# LED_Driver_and_LEDs_04.net
KiCad netlist of a schematic drawn in Altium Designer
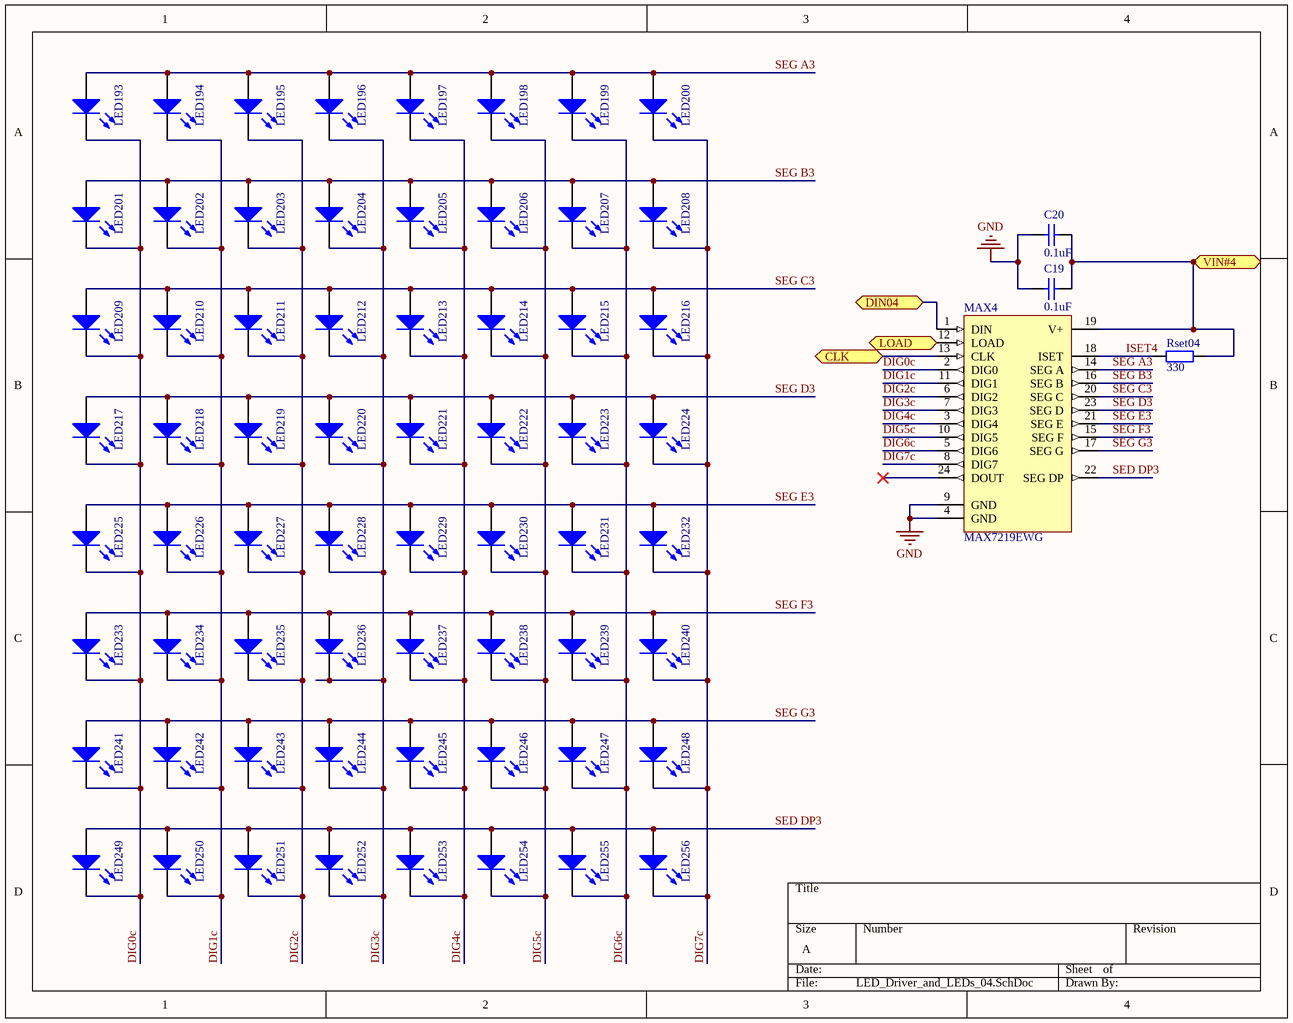
[diagram p0: LED_Driver_and_LEDs_04.SchDoc]

(export (version "E")
  (design (tool "Eeschema 10.0.6"))
  (components
    (comp (ref "C19")
      (value "0.1uF")
      (footprint "6-0805_N")
      (description "Capacitor (Semiconductor SIM Model)")
      (fields (field (name "Comment") "Cap Semi") (field (name "PUBLISHER") "Altium Limited"))
      (libsource (lib "Miscellaneous Devices") (part "Cap Semi"))
    )
    (comp (ref "C20")
      (value "0.1uF")
      (footprint "6-0805_N")
      (description "Capacitor (Semiconductor SIM Model)")
      (fields (field (name "Comment") "Cap Semi") (field (name "PUBLISHER") "Altium Limited"))
      (libsource (lib "Miscellaneous Devices") (part "Cap Semi"))
    )
    (comp (ref "LED193")
      (value "LED3")
      (footprint "3.5X2.8X1.9")
      (description "Typical BLUE SiC LED")
      (fields (field (name "PUBLISHER") "Altium Limited"))
      (libsource (lib "Miscellaneous Devices") (part "LED3"))
    )
    (comp (ref "LED194")
      (value "LED3")
      (footprint "3.5X2.8X1.9")
      (description "Typical BLUE SiC LED")
      (fields (field (name "PUBLISHER") "Altium Limited"))
      (libsource (lib "Miscellaneous Devices") (part "LED3"))
    )
    (comp (ref "LED195")
      (value "LED3")
      (footprint "3.5X2.8X1.9")
      (description "Typical BLUE SiC LED")
      (fields (field (name "PUBLISHER") "Altium Limited"))
      (libsource (lib "Miscellaneous Devices") (part "LED3"))
    )
    (comp (ref "LED196")
      (value "LED3")
      (footprint "3.5X2.8X1.9")
      (description "Typical BLUE SiC LED")
      (fields (field (name "PUBLISHER") "Altium Limited"))
      (libsource (lib "Miscellaneous Devices") (part "LED3"))
    )
    (comp (ref "LED197")
      (value "LED3")
      (footprint "3.5X2.8X1.9")
      (description "Typical BLUE SiC LED")
      (fields (field (name "PUBLISHER") "Altium Limited"))
      (libsource (lib "Miscellaneous Devices") (part "LED3"))
    )
    (comp (ref "LED198")
      (value "LED3")
      (footprint "3.5X2.8X1.9")
      (description "Typical BLUE SiC LED")
      (fields (field (name "PUBLISHER") "Altium Limited"))
      (libsource (lib "Miscellaneous Devices") (part "LED3"))
    )
    (comp (ref "LED199")
      (value "LED3")
      (footprint "3.5X2.8X1.9")
      (description "Typical BLUE SiC LED")
      (fields (field (name "PUBLISHER") "Altium Limited"))
      (libsource (lib "Miscellaneous Devices") (part "LED3"))
    )
    (comp (ref "LED200")
      (value "LED3")
      (footprint "3.5X2.8X1.9")
      (description "Typical BLUE SiC LED")
      (fields (field (name "PUBLISHER") "Altium Limited"))
      (libsource (lib "Miscellaneous Devices") (part "LED3"))
    )
    (comp (ref "LED201")
      (value "LED3")
      (footprint "3.5X2.8X1.9")
      (description "Typical BLUE SiC LED")
      (fields (field (name "PUBLISHER") "Altium Limited"))
      (libsource (lib "Miscellaneous Devices") (part "LED3"))
    )
    (comp (ref "LED202")
      (value "LED3")
      (footprint "3.5X2.8X1.9")
      (description "Typical BLUE SiC LED")
      (fields (field (name "PUBLISHER") "Altium Limited"))
      (libsource (lib "Miscellaneous Devices") (part "LED3"))
    )
    (comp (ref "LED203")
      (value "LED3")
      (footprint "3.5X2.8X1.9")
      (description "Typical BLUE SiC LED")
      (fields (field (name "PUBLISHER") "Altium Limited"))
      (libsource (lib "Miscellaneous Devices") (part "LED3"))
    )
    (comp (ref "LED204")
      (value "LED3")
      (footprint "3.5X2.8X1.9")
      (description "Typical BLUE SiC LED")
      (fields (field (name "PUBLISHER") "Altium Limited"))
      (libsource (lib "Miscellaneous Devices") (part "LED3"))
    )
    (comp (ref "LED205")
      (value "LED3")
      (footprint "3.5X2.8X1.9")
      (description "Typical BLUE SiC LED")
      (fields (field (name "PUBLISHER") "Altium Limited"))
      (libsource (lib "Miscellaneous Devices") (part "LED3"))
    )
    (comp (ref "LED206")
      (value "LED3")
      (footprint "3.5X2.8X1.9")
      (description "Typical BLUE SiC LED")
      (fields (field (name "PUBLISHER") "Altium Limited"))
      (libsource (lib "Miscellaneous Devices") (part "LED3"))
    )
    (comp (ref "LED207")
      (value "LED3")
      (footprint "3.5X2.8X1.9")
      (description "Typical BLUE SiC LED")
      (fields (field (name "PUBLISHER") "Altium Limited"))
      (libsource (lib "Miscellaneous Devices") (part "LED3"))
    )
    (comp (ref "LED208")
      (value "LED3")
      (footprint "3.5X2.8X1.9")
      (description "Typical BLUE SiC LED")
      (fields (field (name "PUBLISHER") "Altium Limited"))
      (libsource (lib "Miscellaneous Devices") (part "LED3"))
    )
    (comp (ref "LED209")
      (value "LED3")
      (footprint "3.5X2.8X1.9")
      (description "Typical BLUE SiC LED")
      (fields (field (name "PUBLISHER") "Altium Limited"))
      (libsource (lib "Miscellaneous Devices") (part "LED3"))
    )
    (comp (ref "LED210")
      (value "LED3")
      (footprint "3.5X2.8X1.9")
      (description "Typical BLUE SiC LED")
      (fields (field (name "PUBLISHER") "Altium Limited"))
      (libsource (lib "Miscellaneous Devices") (part "LED3"))
    )
    (comp (ref "LED211")
      (value "LED3")
      (footprint "3.5X2.8X1.9")
      (description "Typical BLUE SiC LED")
      (fields (field (name "PUBLISHER") "Altium Limited"))
      (libsource (lib "Miscellaneous Devices") (part "LED3"))
    )
    (comp (ref "LED212")
      (value "LED3")
      (footprint "3.5X2.8X1.9")
      (description "Typical BLUE SiC LED")
      (fields (field (name "PUBLISHER") "Altium Limited"))
      (libsource (lib "Miscellaneous Devices") (part "LED3"))
    )
    (comp (ref "LED213")
      (value "LED3")
      (footprint "3.5X2.8X1.9")
      (description "Typical BLUE SiC LED")
      (fields (field (name "PUBLISHER") "Altium Limited"))
      (libsource (lib "Miscellaneous Devices") (part "LED3"))
    )
    (comp (ref "LED214")
      (value "LED3")
      (footprint "3.5X2.8X1.9")
      (description "Typical BLUE SiC LED")
      (fields (field (name "PUBLISHER") "Altium Limited"))
      (libsource (lib "Miscellaneous Devices") (part "LED3"))
    )
    (comp (ref "LED215")
      (value "LED3")
      (footprint "3.5X2.8X1.9")
      (description "Typical BLUE SiC LED")
      (fields (field (name "PUBLISHER") "Altium Limited"))
      (libsource (lib "Miscellaneous Devices") (part "LED3"))
    )
    (comp (ref "LED216")
      (value "LED3")
      (footprint "3.5X2.8X1.9")
      (description "Typical BLUE SiC LED")
      (fields (field (name "PUBLISHER") "Altium Limited"))
      (libsource (lib "Miscellaneous Devices") (part "LED3"))
    )
    (comp (ref "LED217")
      (value "LED3")
      (footprint "3.5X2.8X1.9")
      (description "Typical BLUE SiC LED")
      (fields (field (name "PUBLISHER") "Altium Limited"))
      (libsource (lib "Miscellaneous Devices") (part "LED3"))
    )
    (comp (ref "LED218")
      (value "LED3")
      (footprint "3.5X2.8X1.9")
      (description "Typical BLUE SiC LED")
      (fields (field (name "PUBLISHER") "Altium Limited"))
      (libsource (lib "Miscellaneous Devices") (part "LED3"))
    )
    (comp (ref "LED219")
      (value "LED3")
      (footprint "3.5X2.8X1.9")
      (description "Typical BLUE SiC LED")
      (fields (field (name "PUBLISHER") "Altium Limited"))
      (libsource (lib "Miscellaneous Devices") (part "LED3"))
    )
    (comp (ref "LED220")
      (value "LED3")
      (footprint "3.5X2.8X1.9")
      (description "Typical BLUE SiC LED")
      (fields (field (name "PUBLISHER") "Altium Limited"))
      (libsource (lib "Miscellaneous Devices") (part "LED3"))
    )
    (comp (ref "LED221")
      (value "LED3")
      (footprint "3.5X2.8X1.9")
      (description "Typical BLUE SiC LED")
      (fields (field (name "PUBLISHER") "Altium Limited"))
      (libsource (lib "Miscellaneous Devices") (part "LED3"))
    )
    (comp (ref "LED222")
      (value "LED3")
      (footprint "3.5X2.8X1.9")
      (description "Typical BLUE SiC LED")
      (fields (field (name "PUBLISHER") "Altium Limited"))
      (libsource (lib "Miscellaneous Devices") (part "LED3"))
    )
    (comp (ref "LED223")
      (value "LED3")
      (footprint "3.5X2.8X1.9")
      (description "Typical BLUE SiC LED")
      (fields (field (name "PUBLISHER") "Altium Limited"))
      (libsource (lib "Miscellaneous Devices") (part "LED3"))
    )
    (comp (ref "LED224")
      (value "LED3")
      (footprint "3.5X2.8X1.9")
      (description "Typical BLUE SiC LED")
      (fields (field (name "PUBLISHER") "Altium Limited"))
      (libsource (lib "Miscellaneous Devices") (part "LED3"))
    )
    (comp (ref "LED225")
      (value "LED3")
      (footprint "3.5X2.8X1.9")
      (description "Typical BLUE SiC LED")
      (fields (field (name "PUBLISHER") "Altium Limited"))
      (libsource (lib "Miscellaneous Devices") (part "LED3"))
    )
    (comp (ref "LED226")
      (value "LED3")
      (footprint "3.5X2.8X1.9")
      (description "Typical BLUE SiC LED")
      (fields (field (name "PUBLISHER") "Altium Limited"))
      (libsource (lib "Miscellaneous Devices") (part "LED3"))
    )
    (comp (ref "LED227")
      (value "LED3")
      (footprint "3.5X2.8X1.9")
      (description "Typical BLUE SiC LED")
      (fields (field (name "PUBLISHER") "Altium Limited"))
      (libsource (lib "Miscellaneous Devices") (part "LED3"))
    )
    (comp (ref "LED228")
      (value "LED3")
      (footprint "3.5X2.8X1.9")
      (description "Typical BLUE SiC LED")
      (fields (field (name "PUBLISHER") "Altium Limited"))
      (libsource (lib "Miscellaneous Devices") (part "LED3"))
    )
    (comp (ref "LED229")
      (value "LED3")
      (footprint "3.5X2.8X1.9")
      (description "Typical BLUE SiC LED")
      (fields (field (name "PUBLISHER") "Altium Limited"))
      (libsource (lib "Miscellaneous Devices") (part "LED3"))
    )
    (comp (ref "LED230")
      (value "LED3")
      (footprint "3.5X2.8X1.9")
      (description "Typical BLUE SiC LED")
      (fields (field (name "PUBLISHER") "Altium Limited"))
      (libsource (lib "Miscellaneous Devices") (part "LED3"))
    )
    (comp (ref "LED231")
      (value "LED3")
      (footprint "3.5X2.8X1.9")
      (description "Typical BLUE SiC LED")
      (fields (field (name "PUBLISHER") "Altium Limited"))
      (libsource (lib "Miscellaneous Devices") (part "LED3"))
    )
    (comp (ref "LED232")
      (value "LED3")
      (footprint "3.5X2.8X1.9")
      (description "Typical BLUE SiC LED")
      (fields (field (name "PUBLISHER") "Altium Limited"))
      (libsource (lib "Miscellaneous Devices") (part "LED3"))
    )
    (comp (ref "LED233")
      (value "LED3")
      (footprint "3.5X2.8X1.9")
      (description "Typical BLUE SiC LED")
      (fields (field (name "PUBLISHER") "Altium Limited"))
      (libsource (lib "Miscellaneous Devices") (part "LED3"))
    )
    (comp (ref "LED234")
      (value "LED3")
      (footprint "3.5X2.8X1.9")
      (description "Typical BLUE SiC LED")
      (fields (field (name "PUBLISHER") "Altium Limited"))
      (libsource (lib "Miscellaneous Devices") (part "LED3"))
    )
    (comp (ref "LED235")
      (value "LED3")
      (footprint "3.5X2.8X1.9")
      (description "Typical BLUE SiC LED")
      (fields (field (name "PUBLISHER") "Altium Limited"))
      (libsource (lib "Miscellaneous Devices") (part "LED3"))
    )
    (comp (ref "LED236")
      (value "LED3")
      (footprint "3.5X2.8X1.9")
      (description "Typical BLUE SiC LED")
      (fields (field (name "PUBLISHER") "Altium Limited"))
      (libsource (lib "Miscellaneous Devices") (part "LED3"))
    )
    (comp (ref "LED237")
      (value "LED3")
      (footprint "3.5X2.8X1.9")
      (description "Typical BLUE SiC LED")
      (fields (field (name "PUBLISHER") "Altium Limited"))
      (libsource (lib "Miscellaneous Devices") (part "LED3"))
    )
    (comp (ref "LED238")
      (value "LED3")
      (footprint "3.5X2.8X1.9")
      (description "Typical BLUE SiC LED")
      (fields (field (name "PUBLISHER") "Altium Limited"))
      (libsource (lib "Miscellaneous Devices") (part "LED3"))
    )
    (comp (ref "LED239")
      (value "LED3")
      (footprint "3.5X2.8X1.9")
      (description "Typical BLUE SiC LED")
      (fields (field (name "PUBLISHER") "Altium Limited"))
      (libsource (lib "Miscellaneous Devices") (part "LED3"))
    )
    (comp (ref "LED240")
      (value "LED3")
      (footprint "3.5X2.8X1.9")
      (description "Typical BLUE SiC LED")
      (fields (field (name "PUBLISHER") "Altium Limited"))
      (libsource (lib "Miscellaneous Devices") (part "LED3"))
    )
    (comp (ref "LED241")
      (value "LED3")
      (footprint "3.5X2.8X1.9")
      (description "Typical BLUE SiC LED")
      (fields (field (name "PUBLISHER") "Altium Limited"))
      (libsource (lib "Miscellaneous Devices") (part "LED3"))
    )
    (comp (ref "LED242")
      (value "LED3")
      (footprint "3.5X2.8X1.9")
      (description "Typical BLUE SiC LED")
      (fields (field (name "PUBLISHER") "Altium Limited"))
      (libsource (lib "Miscellaneous Devices") (part "LED3"))
    )
    (comp (ref "LED243")
      (value "LED3")
      (footprint "3.5X2.8X1.9")
      (description "Typical BLUE SiC LED")
      (fields (field (name "PUBLISHER") "Altium Limited"))
      (libsource (lib "Miscellaneous Devices") (part "LED3"))
    )
    (comp (ref "LED244")
      (value "LED3")
      (footprint "3.5X2.8X1.9")
      (description "Typical BLUE SiC LED")
      (fields (field (name "PUBLISHER") "Altium Limited"))
      (libsource (lib "Miscellaneous Devices") (part "LED3"))
    )
    (comp (ref "LED245")
      (value "LED3")
      (footprint "3.5X2.8X1.9")
      (description "Typical BLUE SiC LED")
      (fields (field (name "PUBLISHER") "Altium Limited"))
      (libsource (lib "Miscellaneous Devices") (part "LED3"))
    )
    (comp (ref "LED246")
      (value "LED3")
      (footprint "3.5X2.8X1.9")
      (description "Typical BLUE SiC LED")
      (fields (field (name "PUBLISHER") "Altium Limited"))
      (libsource (lib "Miscellaneous Devices") (part "LED3"))
    )
    (comp (ref "LED247")
      (value "LED3")
      (footprint "3.5X2.8X1.9")
      (description "Typical BLUE SiC LED")
      (fields (field (name "PUBLISHER") "Altium Limited"))
      (libsource (lib "Miscellaneous Devices") (part "LED3"))
    )
    (comp (ref "LED248")
      (value "LED3")
      (footprint "3.5X2.8X1.9")
      (description "Typical BLUE SiC LED")
      (fields (field (name "PUBLISHER") "Altium Limited"))
      (libsource (lib "Miscellaneous Devices") (part "LED3"))
    )
    (comp (ref "LED249")
      (value "LED3")
      (footprint "3.5X2.8X1.9")
      (description "Typical BLUE SiC LED")
      (fields (field (name "PUBLISHER") "Altium Limited"))
      (libsource (lib "Miscellaneous Devices") (part "LED3"))
    )
    (comp (ref "LED250")
      (value "LED3")
      (footprint "3.5X2.8X1.9")
      (description "Typical BLUE SiC LED")
      (fields (field (name "PUBLISHER") "Altium Limited"))
      (libsource (lib "Miscellaneous Devices") (part "LED3"))
    )
    (comp (ref "LED251")
      (value "LED3")
      (footprint "3.5X2.8X1.9")
      (description "Typical BLUE SiC LED")
      (fields (field (name "PUBLISHER") "Altium Limited"))
      (libsource (lib "Miscellaneous Devices") (part "LED3"))
    )
    (comp (ref "LED252")
      (value "LED3")
      (footprint "3.5X2.8X1.9")
      (description "Typical BLUE SiC LED")
      (fields (field (name "PUBLISHER") "Altium Limited"))
      (libsource (lib "Miscellaneous Devices") (part "LED3"))
    )
    (comp (ref "LED253")
      (value "LED3")
      (footprint "3.5X2.8X1.9")
      (description "Typical BLUE SiC LED")
      (fields (field (name "PUBLISHER") "Altium Limited"))
      (libsource (lib "Miscellaneous Devices") (part "LED3"))
    )
    (comp (ref "LED254")
      (value "LED3")
      (footprint "3.5X2.8X1.9")
      (description "Typical BLUE SiC LED")
      (fields (field (name "PUBLISHER") "Altium Limited"))
      (libsource (lib "Miscellaneous Devices") (part "LED3"))
    )
    (comp (ref "LED255")
      (value "LED3")
      (footprint "3.5X2.8X1.9")
      (description "Typical BLUE SiC LED")
      (fields (field (name "PUBLISHER") "Altium Limited"))
      (libsource (lib "Miscellaneous Devices") (part "LED3"))
    )
    (comp (ref "LED256")
      (value "LED3")
      (footprint "3.5X2.8X1.9")
      (description "Typical BLUE SiC LED")
      (fields (field (name "PUBLISHER") "Altium Limited"))
      (libsource (lib "Miscellaneous Devices") (part "LED3"))
    )
    (comp (ref "MAX4")
      (value "MAX7219EWG")
      (footprint "WSO24_N")
      (description "Serially Interfaced, 8-Digit LED Display Driver")
      (fields (field (name "PUBLISHER") "Altium Limited"))
      (libsource (lib "Maxim Interface Display Driver") (part "MAX7219EWG"))
    )
    (comp (ref "Rset04")
      (value "330")
      (footprint "J1-0603")
      (description "Resistor")
      (fields (field (name "Comment") "Res2") (field (name "PUBLISHER") "Altium Limited"))
      (libsource (lib "Miscellaneous Devices") (part "Res2"))
    )
  )
  (nets
    (net (code "1") (name "/CLK") (class "Default")
      (node (ref "MAX4") (pin "13") (pinfunction "CLK_13") (pintype "input"))
    )
    (net (code "2") (name "/DIG0c") (class "Default")
      (node (ref "LED193") (pin "2") (pinfunction "K_2") (pintype "passive"))
      (node (ref "LED201") (pin "2") (pinfunction "K_2") (pintype "passive"))
      (node (ref "LED209") (pin "2") (pinfunction "K_2") (pintype "passive"))
      (node (ref "LED217") (pin "2") (pinfunction "K_2") (pintype "passive"))
      (node (ref "LED225") (pin "2") (pinfunction "K_2") (pintype "passive"))
      (node (ref "LED233") (pin "2") (pinfunction "K_2") (pintype "passive"))
      (node (ref "LED241") (pin "2") (pinfunction "K_2") (pintype "passive"))
      (node (ref "LED249") (pin "2") (pinfunction "K_2") (pintype "passive"))
      (node (ref "MAX4") (pin "2") (pinfunction "DIG0_2") (pintype "output"))
    )
    (net (code "3") (name "/DIG1c") (class "Default")
      (node (ref "LED194") (pin "2") (pinfunction "K_2") (pintype "passive"))
      (node (ref "LED202") (pin "2") (pinfunction "K_2") (pintype "passive"))
      (node (ref "LED210") (pin "2") (pinfunction "K_2") (pintype "passive"))
      (node (ref "LED218") (pin "2") (pinfunction "K_2") (pintype "passive"))
      (node (ref "LED226") (pin "2") (pinfunction "K_2") (pintype "passive"))
      (node (ref "LED234") (pin "2") (pinfunction "K_2") (pintype "passive"))
      (node (ref "LED242") (pin "2") (pinfunction "K_2") (pintype "passive"))
      (node (ref "LED250") (pin "2") (pinfunction "K_2") (pintype "passive"))
      (node (ref "MAX4") (pin "11") (pinfunction "DIG1_11") (pintype "output"))
    )
    (net (code "4") (name "/DIG2c") (class "Default")
      (node (ref "LED195") (pin "2") (pinfunction "K_2") (pintype "passive"))
      (node (ref "LED203") (pin "2") (pinfunction "K_2") (pintype "passive"))
      (node (ref "LED211") (pin "2") (pinfunction "K_2") (pintype "passive"))
      (node (ref "LED219") (pin "2") (pinfunction "K_2") (pintype "passive"))
      (node (ref "LED227") (pin "2") (pinfunction "K_2") (pintype "passive"))
      (node (ref "LED235") (pin "2") (pinfunction "K_2") (pintype "passive"))
      (node (ref "LED243") (pin "2") (pinfunction "K_2") (pintype "passive"))
      (node (ref "LED251") (pin "2") (pinfunction "K_2") (pintype "passive"))
      (node (ref "MAX4") (pin "6") (pinfunction "DIG2_6") (pintype "output"))
    )
    (net (code "5") (name "/DIG3c") (class "Default")
      (node (ref "LED196") (pin "2") (pinfunction "K_2") (pintype "passive"))
      (node (ref "LED204") (pin "2") (pinfunction "K_2") (pintype "passive"))
      (node (ref "LED212") (pin "2") (pinfunction "K_2") (pintype "passive"))
      (node (ref "LED220") (pin "2") (pinfunction "K_2") (pintype "passive"))
      (node (ref "LED228") (pin "2") (pinfunction "K_2") (pintype "passive"))
      (node (ref "LED236") (pin "2") (pinfunction "K_2") (pintype "passive"))
      (node (ref "LED244") (pin "2") (pinfunction "K_2") (pintype "passive"))
      (node (ref "LED252") (pin "2") (pinfunction "K_2") (pintype "passive"))
      (node (ref "MAX4") (pin "7") (pinfunction "DIG3_7") (pintype "output"))
    )
    (net (code "6") (name "/DIG4c") (class "Default")
      (node (ref "LED197") (pin "2") (pinfunction "K_2") (pintype "passive"))
      (node (ref "LED205") (pin "2") (pinfunction "K_2") (pintype "passive"))
      (node (ref "LED213") (pin "2") (pinfunction "K_2") (pintype "passive"))
      (node (ref "LED221") (pin "2") (pinfunction "K_2") (pintype "passive"))
      (node (ref "LED229") (pin "2") (pinfunction "K_2") (pintype "passive"))
      (node (ref "LED237") (pin "2") (pinfunction "K_2") (pintype "passive"))
      (node (ref "LED245") (pin "2") (pinfunction "K_2") (pintype "passive"))
      (node (ref "LED253") (pin "2") (pinfunction "K_2") (pintype "passive"))
      (node (ref "MAX4") (pin "3") (pinfunction "DIG4_3") (pintype "output"))
    )
    (net (code "7") (name "/DIG5c") (class "Default")
      (node (ref "LED198") (pin "2") (pinfunction "K_2") (pintype "passive"))
      (node (ref "LED206") (pin "2") (pinfunction "K_2") (pintype "passive"))
      (node (ref "LED214") (pin "2") (pinfunction "K_2") (pintype "passive"))
      (node (ref "LED222") (pin "2") (pinfunction "K_2") (pintype "passive"))
      (node (ref "LED230") (pin "2") (pinfunction "K_2") (pintype "passive"))
      (node (ref "LED238") (pin "2") (pinfunction "K_2") (pintype "passive"))
      (node (ref "LED246") (pin "2") (pinfunction "K_2") (pintype "passive"))
      (node (ref "LED254") (pin "2") (pinfunction "K_2") (pintype "passive"))
      (node (ref "MAX4") (pin "10") (pinfunction "DIG5_10") (pintype "output"))
    )
    (net (code "8") (name "/DIG6c") (class "Default")
      (node (ref "LED199") (pin "2") (pinfunction "K_2") (pintype "passive"))
      (node (ref "LED207") (pin "2") (pinfunction "K_2") (pintype "passive"))
      (node (ref "LED215") (pin "2") (pinfunction "K_2") (pintype "passive"))
      (node (ref "LED223") (pin "2") (pinfunction "K_2") (pintype "passive"))
      (node (ref "LED231") (pin "2") (pinfunction "K_2") (pintype "passive"))
      (node (ref "LED239") (pin "2") (pinfunction "K_2") (pintype "passive"))
      (node (ref "LED247") (pin "2") (pinfunction "K_2") (pintype "passive"))
      (node (ref "LED255") (pin "2") (pinfunction "K_2") (pintype "passive"))
      (node (ref "MAX4") (pin "5") (pinfunction "DIG6_5") (pintype "output"))
    )
    (net (code "9") (name "/DIG7c") (class "Default")
      (node (ref "LED200") (pin "2") (pinfunction "K_2") (pintype "passive"))
      (node (ref "LED208") (pin "2") (pinfunction "K_2") (pintype "passive"))
      (node (ref "LED216") (pin "2") (pinfunction "K_2") (pintype "passive"))
      (node (ref "LED224") (pin "2") (pinfunction "K_2") (pintype "passive"))
      (node (ref "LED232") (pin "2") (pinfunction "K_2") (pintype "passive"))
      (node (ref "LED240") (pin "2") (pinfunction "K_2") (pintype "passive"))
      (node (ref "LED248") (pin "2") (pinfunction "K_2") (pintype "passive"))
      (node (ref "LED256") (pin "2") (pinfunction "K_2") (pintype "passive"))
      (node (ref "MAX4") (pin "8") (pinfunction "DIG7_8") (pintype "output"))
    )
    (net (code "10") (name "/DIN04") (class "Default")
      (node (ref "MAX4") (pin "1") (pinfunction "DIN_1") (pintype "input"))
    )
    (net (code "11") (name "/ISET4") (class "Default")
      (node (ref "MAX4") (pin "18") (pinfunction "ISET_18") (pintype "passive"))
      (node (ref "Rset04") (pin "2") (pinfunction "2_2") (pintype "passive"))
    )
    (net (code "12") (name "/LOAD") (class "Default")
      (node (ref "MAX4") (pin "12") (pinfunction "LOAD_12") (pintype "input"))
    )
    (net (code "13") (name "/SED DP3") (class "Default")
      (node (ref "LED249") (pin "1") (pinfunction "A_1") (pintype "passive"))
      (node (ref "LED250") (pin "1") (pinfunction "A_1") (pintype "passive"))
      (node (ref "LED251") (pin "1") (pinfunction "A_1") (pintype "passive"))
      (node (ref "LED252") (pin "1") (pinfunction "A_1") (pintype "passive"))
      (node (ref "LED253") (pin "1") (pinfunction "A_1") (pintype "passive"))
      (node (ref "LED254") (pin "1") (pinfunction "A_1") (pintype "passive"))
      (node (ref "LED255") (pin "1") (pinfunction "A_1") (pintype "passive"))
      (node (ref "LED256") (pin "1") (pinfunction "A_1") (pintype "passive"))
      (node (ref "MAX4") (pin "22") (pinfunction "SEG_DP_22") (pintype "output"))
    )
    (net (code "14") (name "/SEG A3") (class "Default")
      (node (ref "LED193") (pin "1") (pinfunction "A_1") (pintype "passive"))
      (node (ref "LED194") (pin "1") (pinfunction "A_1") (pintype "passive"))
      (node (ref "LED195") (pin "1") (pinfunction "A_1") (pintype "passive"))
      (node (ref "LED196") (pin "1") (pinfunction "A_1") (pintype "passive"))
      (node (ref "LED197") (pin "1") (pinfunction "A_1") (pintype "passive"))
      (node (ref "LED198") (pin "1") (pinfunction "A_1") (pintype "passive"))
      (node (ref "LED199") (pin "1") (pinfunction "A_1") (pintype "passive"))
      (node (ref "LED200") (pin "1") (pinfunction "A_1") (pintype "passive"))
      (node (ref "MAX4") (pin "14") (pinfunction "SEG_A_14") (pintype "output"))
    )
    (net (code "15") (name "/SEG B3") (class "Default")
      (node (ref "LED201") (pin "1") (pinfunction "A_1") (pintype "passive"))
      (node (ref "LED202") (pin "1") (pinfunction "A_1") (pintype "passive"))
      (node (ref "LED203") (pin "1") (pinfunction "A_1") (pintype "passive"))
      (node (ref "LED204") (pin "1") (pinfunction "A_1") (pintype "passive"))
      (node (ref "LED205") (pin "1") (pinfunction "A_1") (pintype "passive"))
      (node (ref "LED206") (pin "1") (pinfunction "A_1") (pintype "passive"))
      (node (ref "LED207") (pin "1") (pinfunction "A_1") (pintype "passive"))
      (node (ref "LED208") (pin "1") (pinfunction "A_1") (pintype "passive"))
      (node (ref "MAX4") (pin "16") (pinfunction "SEG_B_16") (pintype "output"))
    )
    (net (code "16") (name "/SEG C3") (class "Default")
      (node (ref "LED209") (pin "1") (pinfunction "A_1") (pintype "passive"))
      (node (ref "LED210") (pin "1") (pinfunction "A_1") (pintype "passive"))
      (node (ref "LED211") (pin "1") (pinfunction "A_1") (pintype "passive"))
      (node (ref "LED212") (pin "1") (pinfunction "A_1") (pintype "passive"))
      (node (ref "LED213") (pin "1") (pinfunction "A_1") (pintype "passive"))
      (node (ref "LED214") (pin "1") (pinfunction "A_1") (pintype "passive"))
      (node (ref "LED215") (pin "1") (pinfunction "A_1") (pintype "passive"))
      (node (ref "LED216") (pin "1") (pinfunction "A_1") (pintype "passive"))
      (node (ref "MAX4") (pin "20") (pinfunction "SEG_C_20") (pintype "output"))
    )
    (net (code "17") (name "/SEG D3") (class "Default")
      (node (ref "LED217") (pin "1") (pinfunction "A_1") (pintype "passive"))
      (node (ref "LED218") (pin "1") (pinfunction "A_1") (pintype "passive"))
      (node (ref "LED219") (pin "1") (pinfunction "A_1") (pintype "passive"))
      (node (ref "LED220") (pin "1") (pinfunction "A_1") (pintype "passive"))
      (node (ref "LED221") (pin "1") (pinfunction "A_1") (pintype "passive"))
      (node (ref "LED222") (pin "1") (pinfunction "A_1") (pintype "passive"))
      (node (ref "LED223") (pin "1") (pinfunction "A_1") (pintype "passive"))
      (node (ref "LED224") (pin "1") (pinfunction "A_1") (pintype "passive"))
      (node (ref "MAX4") (pin "23") (pinfunction "SEG_D_23") (pintype "output"))
    )
    (net (code "18") (name "/SEG E3") (class "Default")
      (node (ref "LED225") (pin "1") (pinfunction "A_1") (pintype "passive"))
      (node (ref "LED226") (pin "1") (pinfunction "A_1") (pintype "passive"))
      (node (ref "LED227") (pin "1") (pinfunction "A_1") (pintype "passive"))
      (node (ref "LED228") (pin "1") (pinfunction "A_1") (pintype "passive"))
      (node (ref "LED229") (pin "1") (pinfunction "A_1") (pintype "passive"))
      (node (ref "LED230") (pin "1") (pinfunction "A_1") (pintype "passive"))
      (node (ref "LED231") (pin "1") (pinfunction "A_1") (pintype "passive"))
      (node (ref "LED232") (pin "1") (pinfunction "A_1") (pintype "passive"))
      (node (ref "MAX4") (pin "21") (pinfunction "SEG_E_21") (pintype "output"))
    )
    (net (code "19") (name "/SEG F3") (class "Default")
      (node (ref "LED233") (pin "1") (pinfunction "A_1") (pintype "passive"))
      (node (ref "LED234") (pin "1") (pinfunction "A_1") (pintype "passive"))
      (node (ref "LED235") (pin "1") (pinfunction "A_1") (pintype "passive"))
      (node (ref "LED236") (pin "1") (pinfunction "A_1") (pintype "passive"))
      (node (ref "LED237") (pin "1") (pinfunction "A_1") (pintype "passive"))
      (node (ref "LED238") (pin "1") (pinfunction "A_1") (pintype "passive"))
      (node (ref "LED239") (pin "1") (pinfunction "A_1") (pintype "passive"))
      (node (ref "LED240") (pin "1") (pinfunction "A_1") (pintype "passive"))
      (node (ref "MAX4") (pin "15") (pinfunction "SEG_F_15") (pintype "output"))
    )
    (net (code "20") (name "/SEG G3") (class "Default")
      (node (ref "LED241") (pin "1") (pinfunction "A_1") (pintype "passive"))
      (node (ref "LED242") (pin "1") (pinfunction "A_1") (pintype "passive"))
      (node (ref "LED243") (pin "1") (pinfunction "A_1") (pintype "passive"))
      (node (ref "LED244") (pin "1") (pinfunction "A_1") (pintype "passive"))
      (node (ref "LED245") (pin "1") (pinfunction "A_1") (pintype "passive"))
      (node (ref "LED246") (pin "1") (pinfunction "A_1") (pintype "passive"))
      (node (ref "LED247") (pin "1") (pinfunction "A_1") (pintype "passive"))
      (node (ref "LED248") (pin "1") (pinfunction "A_1") (pintype "passive"))
      (node (ref "MAX4") (pin "17") (pinfunction "SEG_G_17") (pintype "output"))
    )
    (net (code "21") (name "/VIN#4") (class "Default")
      (node (ref "C19") (pin "1") (pinfunction "1_1") (pintype "passive"))
      (node (ref "C20") (pin "1") (pinfunction "1_1") (pintype "passive"))
      (node (ref "MAX4") (pin "19") (pinfunction "V+_19") (pintype "power_in"))
      (node (ref "Rset04") (pin "1") (pinfunction "1_1") (pintype "passive"))
    )
    (net (code "22") (name "GND") (class "Default")
      (node (ref "C19") (pin "2") (pinfunction "2_2") (pintype "passive"))
      (node (ref "C20") (pin "2") (pinfunction "2_2") (pintype "passive"))
      (node (ref "MAX4") (pin "4") (pinfunction "GND_4") (pintype "power_in"))
      (node (ref "MAX4") (pin "9") (pinfunction "GND_9") (pintype "power_in"))
    )
    (net (code "23") (name "unconnected-(MAX4-DOUT-Pad24)") (class "Default")
      (node (ref "MAX4") (pin "24") (pinfunction "DOUT_24") (pintype "output+no_connect"))
    )
  )
)
